# LB_BIT_i18_MOTIONTRIGGER-v02_rev1.net
KiCad netlist of a schematic drawn in EAGLE
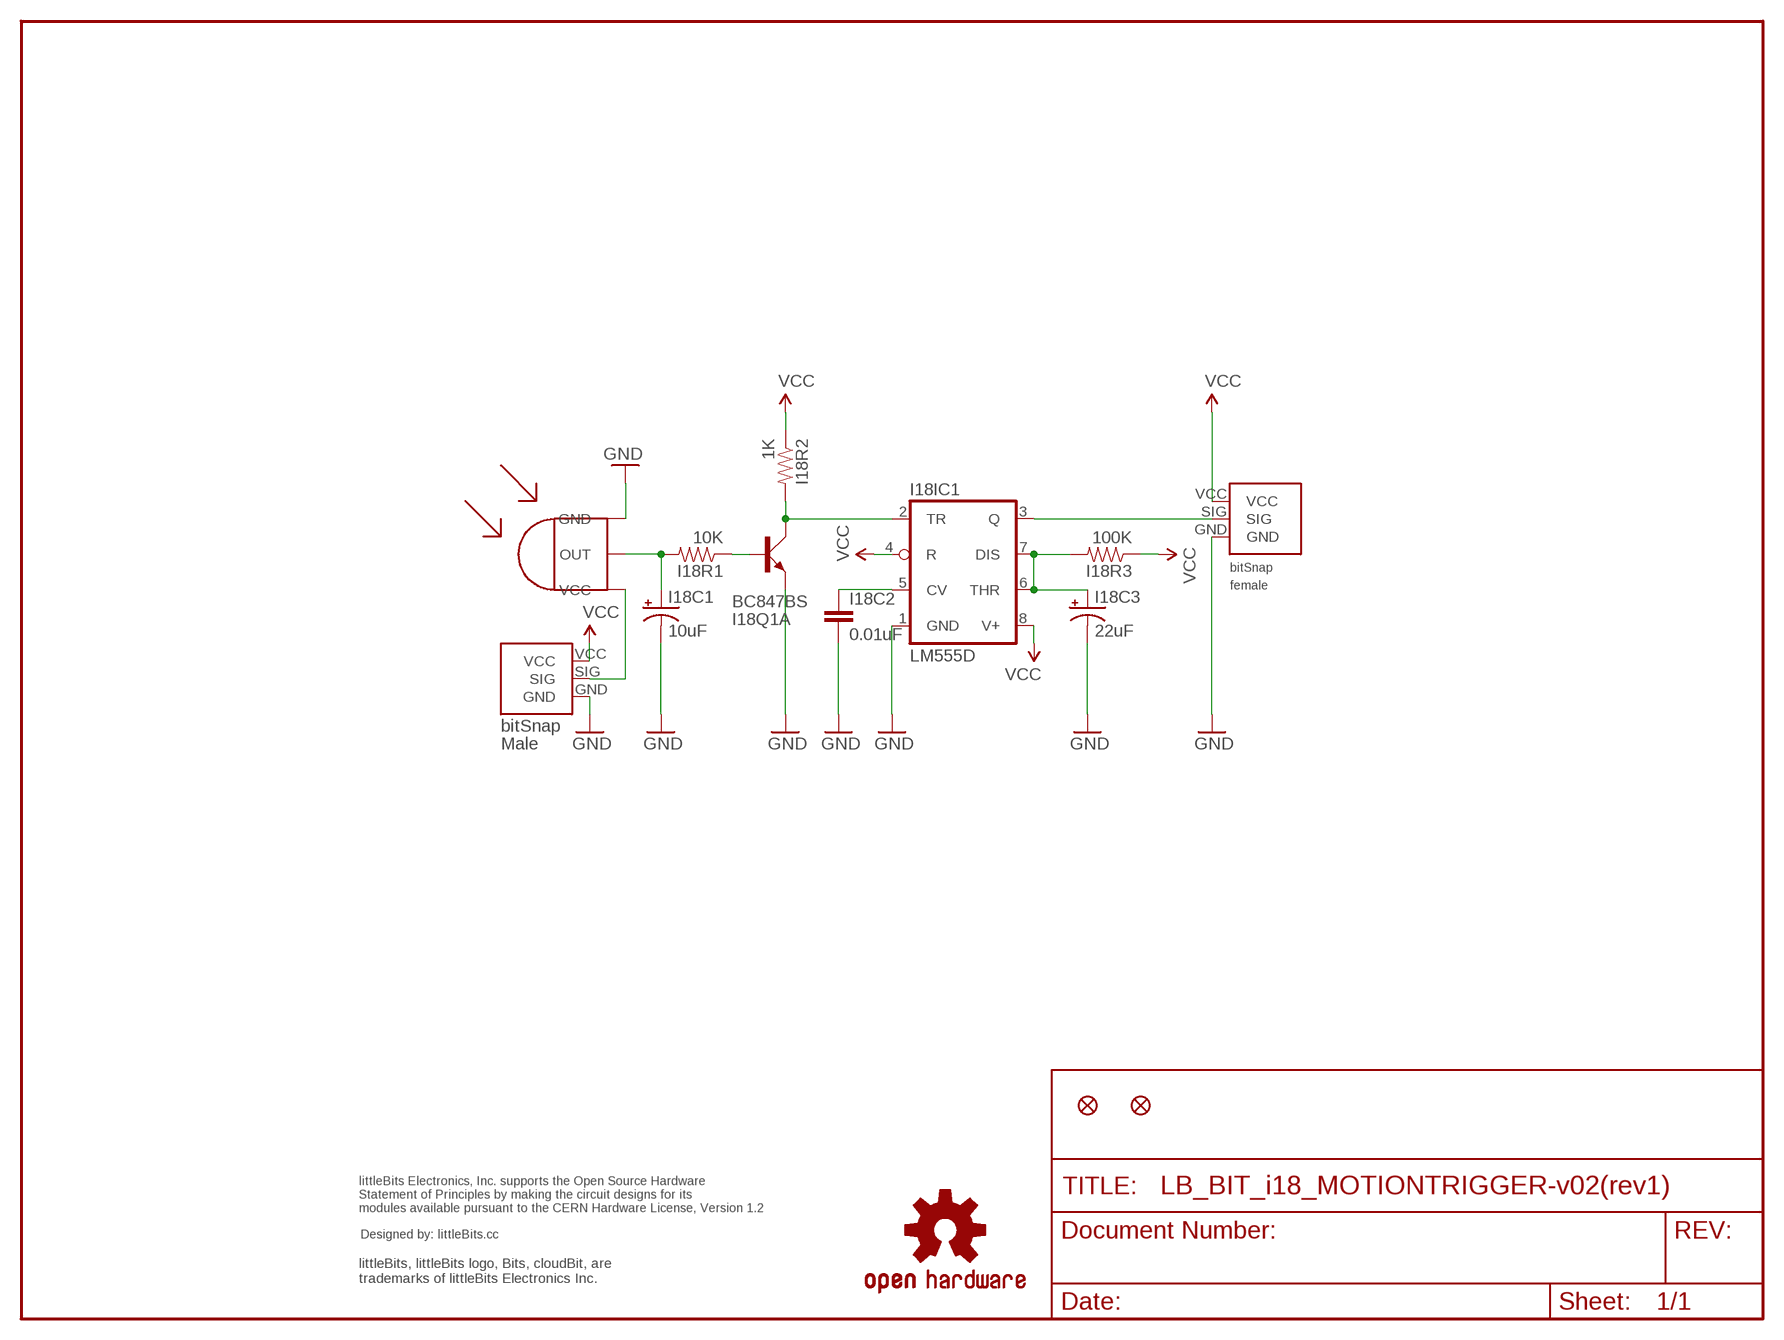
[diagram p0: schematic, sheet 1]

(export (version "E")
  (design (tool "Eeschema 10.0.6"))
  (components
    (comp (ref "I18BSF")
      (value "BITSNAP_FEMALE")
      (footprint "eagle-import:BITSNAP_FEMALE")
      (libsource (lib "eagle-import") (part "BITSNAP_FEMALE"))
    )
    (comp (ref "I18BSM")
      (value "BITSNAP_MALE")
      (footprint "eagle-import:BITSNAP_MALE")
      (libsource (lib "eagle-import") (part "BITSNAP_MALE"))
    )
    (comp (ref "I18C1")
      (value "10uF")
      (footprint "eagle-import:EIA3216")
      (libsource (lib "eagle-import") (part "CAP_POL1206"))
    )
    (comp (ref "I18C2")
      (value "0.01uF")
      (footprint "eagle-import:0603-CAP")
      (libsource (lib "eagle-import") (part "CAP0603-CAP"))
    )
    (comp (ref "I18C3")
      (value "22uF")
      (footprint "eagle-import:EIA3216")
      (libsource (lib "eagle-import") (part "CAP_POL1206"))
    )
    (comp (ref "I18FD1")
      (value "FIDUCIAL1X2")
      (footprint "eagle-import:FIDUCIAL-1X2")
      (libsource (lib "eagle-import") (part "FIDUCIAL1X2"))
    )
    (comp (ref "I18FD2")
      (value "FIDUCIAL1X2")
      (footprint "eagle-import:FIDUCIAL-1X2")
      (libsource (lib "eagle-import") (part "FIDUCIAL1X2"))
    )
    (comp (ref "I18IC1")
      (value "LM555D")
      (footprint "eagle-import:SO08")
      (libsource (lib "eagle-import") (part "555DLM"))
    )
    (comp (ref "I18Q1")
      (value "BC847BS")
      (footprint "eagle-import:SOT363_PHILIPS")
      (libsource (lib "eagle-import") (part "BC847BS"))
    )
    (comp (ref "I18R1")
      (value "10K")
      (footprint "eagle-import:0603-RES")
      (libsource (lib "eagle-import") (part "RESISTOR0603-RES"))
    )
    (comp (ref "I18R2")
      (value "1K")
      (footprint "eagle-import:0603-RES")
      (libsource (lib "eagle-import") (part "RESISTOR0603-RES"))
    )
    (comp (ref "I18R3")
      (value "100K")
      (footprint "eagle-import:0603-RES")
      (libsource (lib "eagle-import") (part "RESISTOR0603-RES"))
    )
    (comp (ref "I18U1")
      (value "PIR-EKMC1601112")
      (footprint "eagle-import:PIR-EKMC1601112")
      (libsource (lib "eagle-import") (part "PIR-EKMC1601112"))
    )
    (comp (ref "U$1")
      (value "OSHWCREDIT")
      (footprint "eagle-import:OSHWCREDIT")
      (libsource (lib "eagle-import") (part "OSHWCREDIT"))
    )
    (comp (ref "U$2")
      (value "OSHW-LOGOL")
      (footprint "eagle-import:OSHW-LOGO-L")
      (libsource (lib "eagle-import") (part "OSHW-LOGOL"))
    )
  )
  (nets
    (net (code "1") (name "GND") (class "Default")
      (node (ref "I18BSF") (pin "GND") (pinfunction "GND_GND") (pintype "bidirectional"))
      (node (ref "I18BSM") (pin "GND") (pinfunction "GND_GND") (pintype "bidirectional"))
      (node (ref "I18C1") (pin "C") (pinfunction "-_C") (pintype "passive"))
      (node (ref "I18C2") (pin "2") (pinfunction "2_2") (pintype "passive"))
      (node (ref "I18C3") (pin "C") (pinfunction "-_C") (pintype "passive"))
      (node (ref "I18IC1") (pin "1") (pinfunction "GND_1") (pintype "power_in"))
      (node (ref "I18Q1") (pin "1") (pinfunction "E_1") (pintype "passive"))
      (node (ref "I18U1") (pin "GND") (pinfunction "GND_GND") (pintype "bidirectional"))
    )
    (net (code "2") (name "Net-(I18BSM-PadSIG)") (class "Default")
      (node (ref "I18BSM") (pin "SIG") (pinfunction "SIG_SIG") (pintype "bidirectional"))
      (node (ref "I18U1") (pin "VCC") (pinfunction "VCC_VCC") (pintype "bidirectional"))
    )
    (net (code "3") (name "Net-(I18C1-+)") (class "Default")
      (node (ref "I18C1") (pin "A") (pinfunction "+_A") (pintype "passive"))
      (node (ref "I18R1") (pin "2") (pinfunction "2_2") (pintype "passive"))
      (node (ref "I18U1") (pin "OUT") (pinfunction "OUT_OUT") (pintype "bidirectional"))
    )
    (net (code "4") (name "Net-(I18C3-+)") (class "Default")
      (node (ref "I18C3") (pin "A") (pinfunction "+_A") (pintype "passive"))
      (node (ref "I18IC1") (pin "6") (pinfunction "THR_6") (pintype "input"))
      (node (ref "I18IC1") (pin "7") (pinfunction "DIS_7") (pintype "input"))
      (node (ref "I18R3") (pin "2") (pinfunction "2_2") (pintype "passive"))
    )
    (net (code "5") (name "Net-(I18IC1-CV)") (class "Default")
      (node (ref "I18C2") (pin "1") (pinfunction "1_1") (pintype "passive"))
      (node (ref "I18IC1") (pin "5") (pinfunction "CV_5") (pintype "input"))
    )
    (net (code "6") (name "Net-(I18IC1-Q)") (class "Default")
      (node (ref "I18BSF") (pin "SIG") (pinfunction "SIG_SIG") (pintype "bidirectional"))
      (node (ref "I18IC1") (pin "3") (pinfunction "Q_3") (pintype "output"))
    )
    (net (code "7") (name "Net-(I18IC1-TR)") (class "Default")
      (node (ref "I18IC1") (pin "2") (pinfunction "TR_2") (pintype "input"))
      (node (ref "I18Q1") (pin "6") (pinfunction "C_6") (pintype "passive"))
      (node (ref "I18R2") (pin "2") (pinfunction "2_2") (pintype "passive"))
    )
    (net (code "8") (name "Net-(I18Q1A-B)") (class "Default")
      (node (ref "I18Q1") (pin "2") (pinfunction "B_2") (pintype "passive"))
      (node (ref "I18R1") (pin "1") (pinfunction "1_1") (pintype "passive"))
    )
    (net (code "9") (name "VCC") (class "Default")
      (node (ref "I18BSF") (pin "VCC") (pinfunction "VCC_VCC") (pintype "bidirectional"))
      (node (ref "I18BSM") (pin "VCC") (pinfunction "VCC_VCC") (pintype "bidirectional"))
      (node (ref "I18IC1") (pin "4") (pinfunction "R_4") (pintype "input"))
      (node (ref "I18IC1") (pin "8") (pinfunction "V+_8") (pintype "power_in"))
      (node (ref "I18R2") (pin "1") (pinfunction "1_1") (pintype "passive"))
      (node (ref "I18R3") (pin "1") (pinfunction "1_1") (pintype "passive"))
    )
  )
)
